# VestibularH2.net
KiCad netlist of a schematic drawn in EAGLE
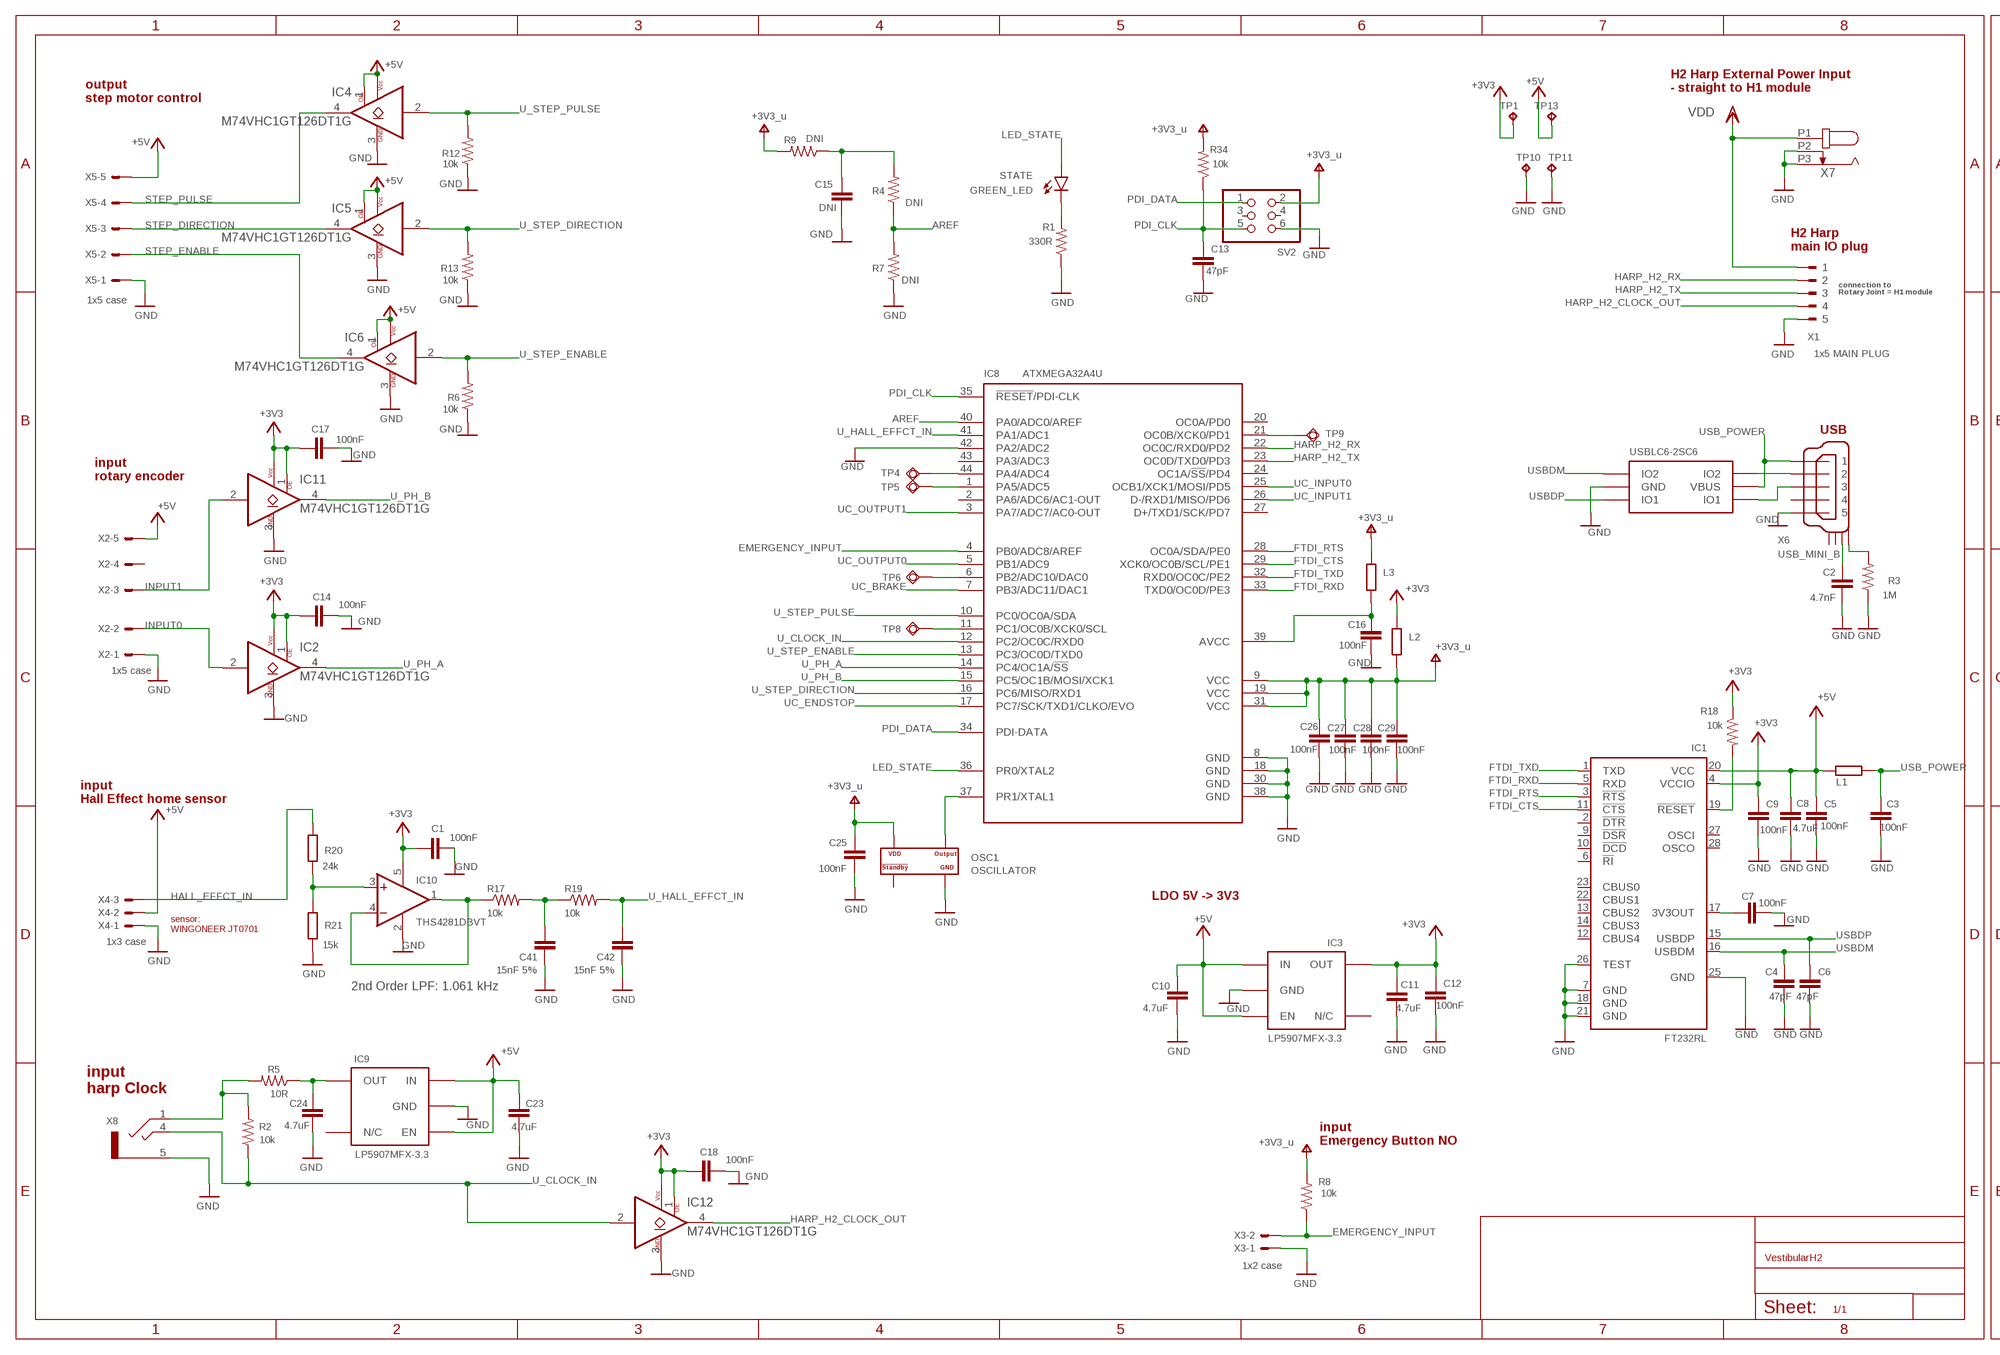
[diagram p0: schematic, sheet 1, part 1 of 2]
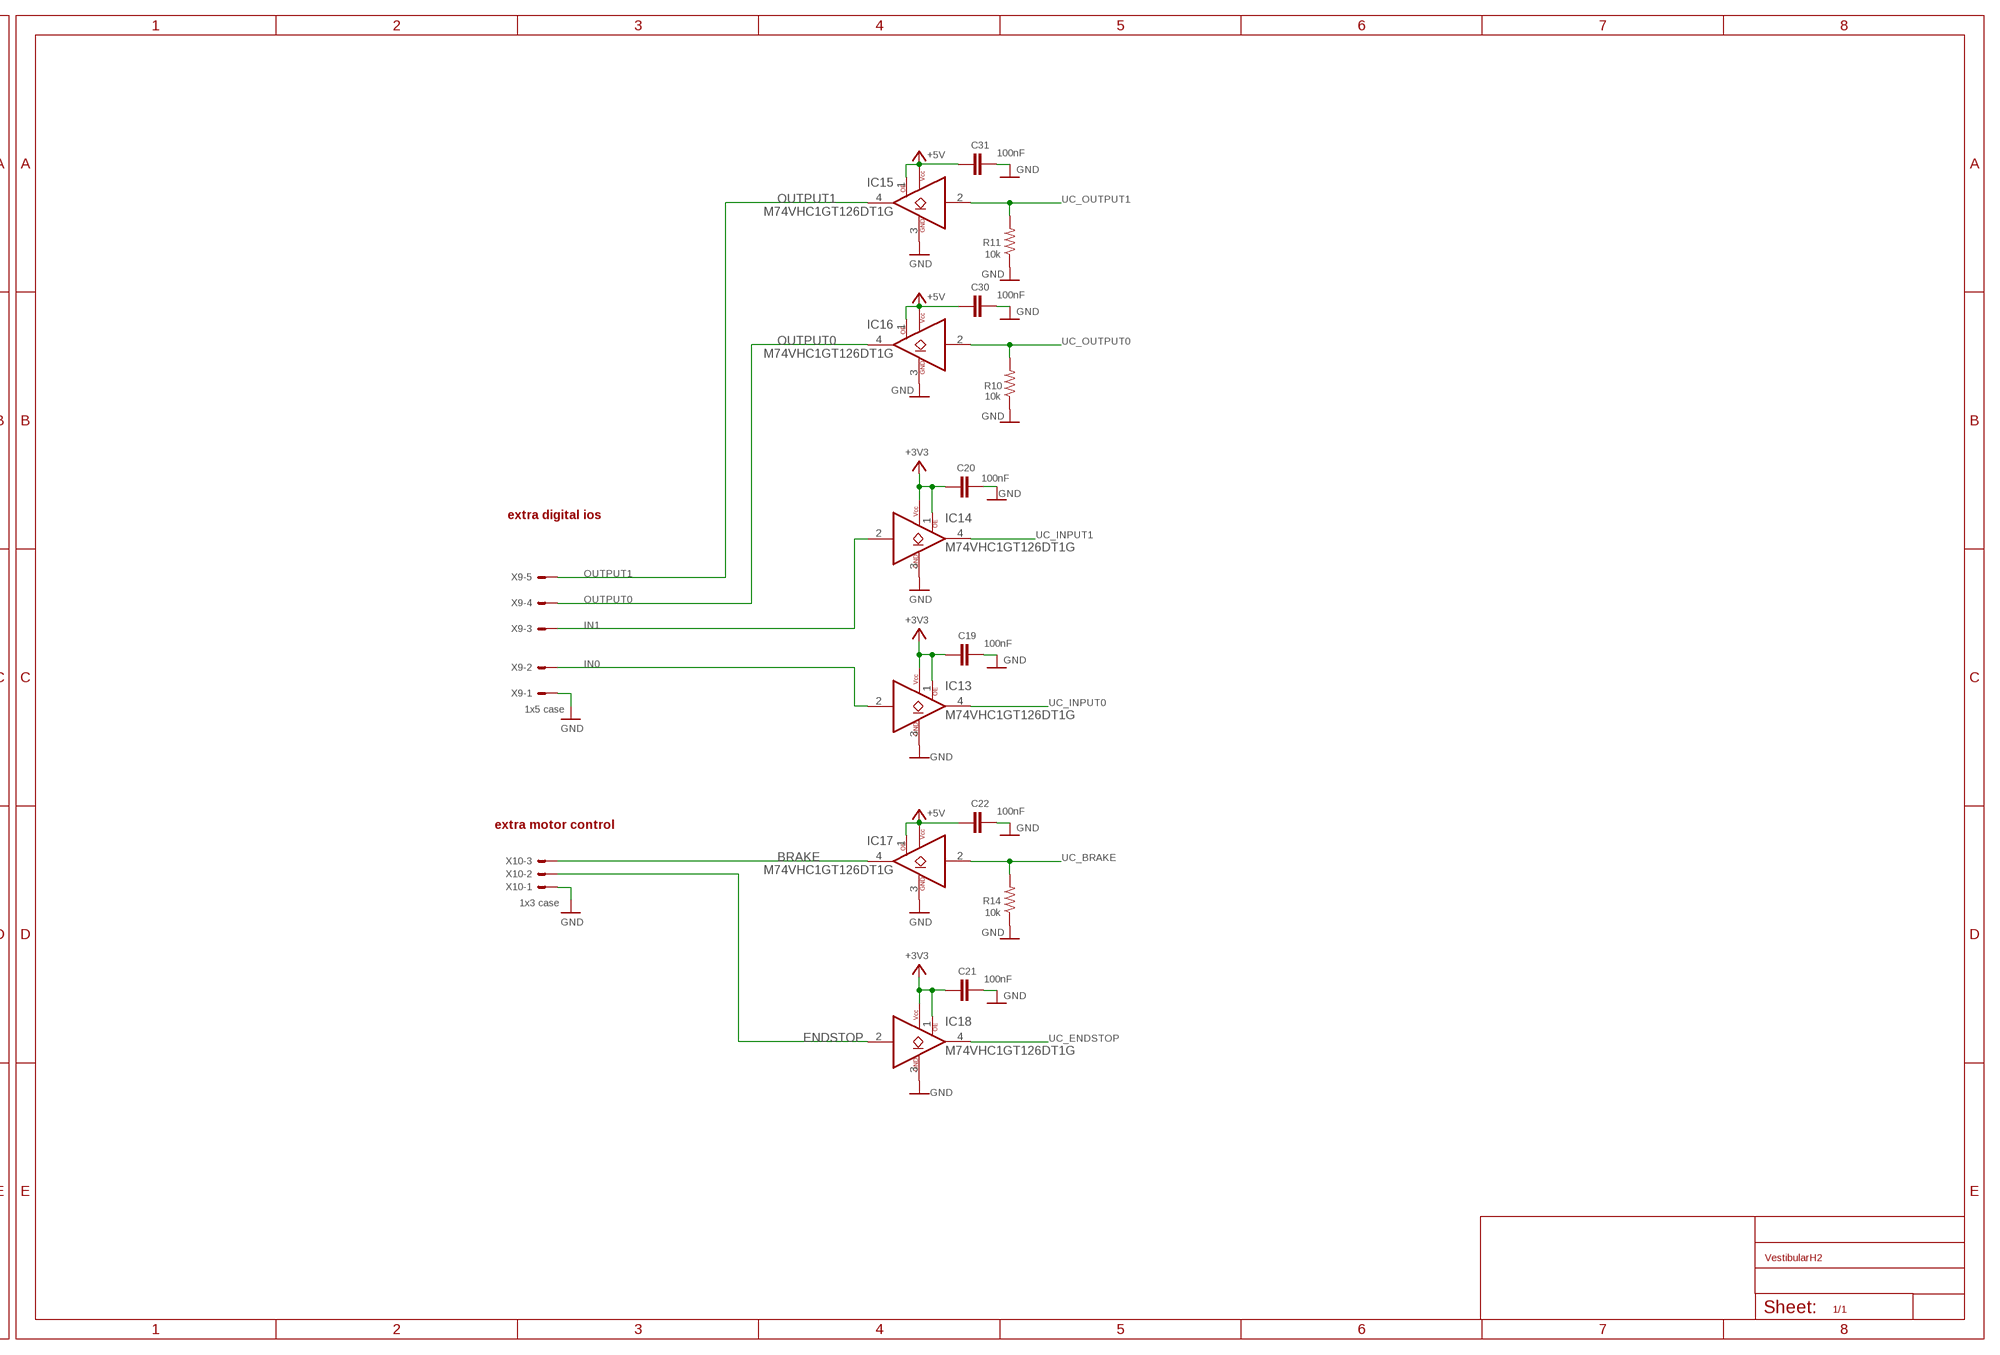
[diagram p1: schematic, sheet 1, part 2 of 2]

(export (version "E")
  (design (tool "Eeschema 10.0.6"))
  (components
    (comp (ref "C1")
      (value "100nF")
      (footprint "eagle-import:C0402K")
      (fields (field (name "MPN") "C1005X7R1H104K050BB"))
      (libsource (lib "eagle-import") (part "C-EUC0402K"))
    )
    (comp (ref "C2")
      (value "4.7nF")
      (footprint "eagle-import:C0402K")
      (fields (field (name "MPN") "CC0402KRX7R8BB472"))
      (libsource (lib "eagle-import") (part "C-EUC0402K"))
    )
    (comp (ref "C3")
      (value "100nF")
      (footprint "eagle-import:C0402K")
      (fields (field (name "MPN") "C1005X7R1H104K050BB"))
      (libsource (lib "eagle-import") (part "C-EUC0402K"))
    )
    (comp (ref "C4")
      (value "47pF")
      (footprint "eagle-import:C0402K")
      (fields (field (name "MPN") "04025A470JAT2A"))
      (libsource (lib "eagle-import") (part "C-EUC0402K"))
    )
    (comp (ref "C5")
      (value "100nF")
      (footprint "eagle-import:C0402K")
      (fields (field (name "MPN") "C1005X7R1H104K050BB"))
      (libsource (lib "eagle-import") (part "C-EUC0402K"))
    )
    (comp (ref "C6")
      (value "47pF")
      (footprint "eagle-import:C0402K")
      (fields (field (name "MPN") "04025A470JAT2A"))
      (libsource (lib "eagle-import") (part "C-EUC0402K"))
    )
    (comp (ref "C7")
      (value "100nF")
      (footprint "eagle-import:C0402K")
      (fields (field (name "MPN") "C1005X7R1H104K050BB"))
      (libsource (lib "eagle-import") (part "C-EUC0402K"))
    )
    (comp (ref "C8")
      (value "4.7uF")
      (footprint "eagle-import:C0603K")
      (fields (field (name "MPN") "C1608X6S1C475K080AC"))
      (libsource (lib "eagle-import") (part "C-EUC0603K"))
    )
    (comp (ref "C9")
      (value "100nF")
      (footprint "eagle-import:C0402K")
      (fields (field (name "MPN") "C1005X7R1H104K050BB"))
      (libsource (lib "eagle-import") (part "C-EUC0402K"))
    )
    (comp (ref "C10")
      (value "4.7uF")
      (footprint "eagle-import:C0603K")
      (fields (field (name "MPN") "C1608X6S1C475K080AC"))
      (libsource (lib "eagle-import") (part "C-EUC0603K"))
    )
    (comp (ref "C11")
      (value "4.7uF")
      (footprint "eagle-import:C0603K")
      (fields (field (name "MPN") "C1608X6S1C475K080AC"))
      (libsource (lib "eagle-import") (part "C-EUC0603K"))
    )
    (comp (ref "C12")
      (value "100nF")
      (footprint "eagle-import:C0402K")
      (fields (field (name "MPN") "C1005X7R1H104K050BB"))
      (libsource (lib "eagle-import") (part "C-EUC0402K"))
    )
    (comp (ref "C13")
      (value "47pF")
      (footprint "eagle-import:C0402K")
      (fields (field (name "MPN") "04025A470JAT2A"))
      (libsource (lib "eagle-import") (part "C-EUC0402K"))
    )
    (comp (ref "C14")
      (value "100nF")
      (footprint "eagle-import:C0402K")
      (fields (field (name "MPN") "C1005X7R1H104K050BB"))
      (libsource (lib "eagle-import") (part "C-EUC0402K"))
    )
    (comp (ref "C15")
      (value "DNI")
      (footprint "eagle-import:C0603K")
      (libsource (lib "eagle-import") (part "C-EUC0603K"))
    )
    (comp (ref "C16")
      (value "100nF")
      (footprint "eagle-import:C0402K")
      (fields (field (name "MPN") "C1005X7R1H104K050BB"))
      (libsource (lib "eagle-import") (part "C-EUC0402K"))
    )
    (comp (ref "C17")
      (value "100nF")
      (footprint "eagle-import:C0402K")
      (fields (field (name "MPN") "C1005X7R1H104K050BB"))
      (libsource (lib "eagle-import") (part "C-EUC0402K"))
    )
    (comp (ref "C18")
      (value "100nF")
      (footprint "eagle-import:C0402K")
      (fields (field (name "MPN") "C1005X7R1H104K050BB"))
      (libsource (lib "eagle-import") (part "C-EUC0402K"))
    )
    (comp (ref "C19")
      (value "100nF")
      (footprint "eagle-import:C0402K")
      (fields (field (name "MPN") "C1005X7R1H104K050BB"))
      (libsource (lib "eagle-import") (part "C-EUC0402K"))
    )
    (comp (ref "C20")
      (value "100nF")
      (footprint "eagle-import:C0402K")
      (fields (field (name "MPN") "C1005X7R1H104K050BB"))
      (libsource (lib "eagle-import") (part "C-EUC0402K"))
    )
    (comp (ref "C21")
      (value "100nF")
      (footprint "eagle-import:C0402K")
      (fields (field (name "MPN") "C1005X7R1H104K050BB"))
      (libsource (lib "eagle-import") (part "C-EUC0402K"))
    )
    (comp (ref "C22")
      (value "100nF")
      (footprint "eagle-import:C0402K")
      (fields (field (name "MPN") "C1005X7R1H104K050BB"))
      (libsource (lib "eagle-import") (part "C-EUC0402K"))
    )
    (comp (ref "C23")
      (value "4.7uF")
      (footprint "eagle-import:C0603K")
      (fields (field (name "MPN") "C1608X6S1C475K080AC"))
      (libsource (lib "eagle-import") (part "C-EUC0603K"))
    )
    (comp (ref "C24")
      (value "4.7uF")
      (footprint "eagle-import:C0603K")
      (fields (field (name "MPN") "C1608X6S1C475K080AC"))
      (libsource (lib "eagle-import") (part "C-EUC0603K"))
    )
    (comp (ref "C25")
      (value "100nF")
      (footprint "eagle-import:C0402K")
      (fields (field (name "MPN") "C1005X7R1H104K050BB"))
      (libsource (lib "eagle-import") (part "C-EUC0402K"))
    )
    (comp (ref "C26")
      (value "100nF")
      (footprint "eagle-import:C0402K")
      (fields (field (name "MPN") "C1005X7R1H104K050BB"))
      (libsource (lib "eagle-import") (part "C-EUC0402K"))
    )
    (comp (ref "C27")
      (value "100nF")
      (footprint "eagle-import:C0402K")
      (fields (field (name "MPN") "C1005X7R1H104K050BB"))
      (libsource (lib "eagle-import") (part "C-EUC0402K"))
    )
    (comp (ref "C28")
      (value "100nF")
      (footprint "eagle-import:C0402K")
      (fields (field (name "MPN") "C1005X7R1H104K050BB"))
      (libsource (lib "eagle-import") (part "C-EUC0402K"))
    )
    (comp (ref "C29")
      (value "100nF")
      (footprint "eagle-import:C0402K")
      (fields (field (name "MPN") "C1005X7R1H104K050BB"))
      (libsource (lib "eagle-import") (part "C-EUC0402K"))
    )
    (comp (ref "C30")
      (value "100nF")
      (footprint "eagle-import:C0402K")
      (fields (field (name "MPN") "C1005X7R1H104K050BB"))
      (libsource (lib "eagle-import") (part "C-EUC0402K"))
    )
    (comp (ref "C31")
      (value "100nF")
      (footprint "eagle-import:C0402K")
      (fields (field (name "MPN") "C1005X7R1H104K050BB"))
      (libsource (lib "eagle-import") (part "C-EUC0402K"))
    )
    (comp (ref "C41")
      (value "15nF 5%")
      (footprint "eagle-import:C0402K")
      (fields (field (name "MPN") "CGA2B3X7R1V153K050BB"))
      (libsource (lib "eagle-import") (part "C-EUC0402K"))
    )
    (comp (ref "C42")
      (value "15nF 5%")
      (footprint "eagle-import:C0402K")
      (fields (field (name "MPN") "CGA2B3X7R1V153K050BB"))
      (libsource (lib "eagle-import") (part "C-EUC0402K"))
    )
    (comp (ref "IC1")
      (value "FT232RL")
      (footprint "eagle-import:SSOP28")
      (libsource (lib "eagle-import") (part "FT232RL"))
    )
    (comp (ref "IC2")
      (value "M74VHC1GT126DT1G")
      (footprint "eagle-import:TSOP-5")
      (libsource (lib "eagle-import") (part "M74VHC1GT126DT1G"))
    )
    (comp (ref "IC3")
      (value "LP5907MFX-3.3")
      (footprint "eagle-import:TSOT23-5")
      (fields (field (name "MPN") "LP5907MFX-3.3/NOPB"))
      (libsource (lib "eagle-import") (part "TLV700XX"))
    )
    (comp (ref "IC4")
      (value "M74VHC1GT126DT1G")
      (footprint "eagle-import:TSOP-5")
      (libsource (lib "eagle-import") (part "M74VHC1GT126DT1G"))
    )
    (comp (ref "IC5")
      (value "M74VHC1GT126DT1G")
      (footprint "eagle-import:TSOP-5")
      (libsource (lib "eagle-import") (part "M74VHC1GT126DT1G"))
    )
    (comp (ref "IC6")
      (value "M74VHC1GT126DT1G")
      (footprint "eagle-import:TSOP-5")
      (libsource (lib "eagle-import") (part "M74VHC1GT126DT1G"))
    )
    (comp (ref "IC7")
      (value "USBLC6-2SC6")
      (footprint "eagle-import:SOT23-6L")
      (libsource (lib "eagle-import") (part "USBLC6-2SC6"))
    )
    (comp (ref "IC8")
      (value "ATXMEGA32A4U")
      (footprint "eagle-import:TQFP44")
      (fields (field (name "MPN") "ATXMEGA32A4U-AUR"))
      (libsource (lib "eagle-import") (part "XMEGA-A4_AT-XMEGA-XXA4-AUTQFP44"))
    )
    (comp (ref "IC9")
      (value "LP5907MFX-3.3")
      (footprint "eagle-import:TSOT23-5")
      (fields (field (name "MPN") "LP5907MFX-3.3/NOPB"))
      (libsource (lib "eagle-import") (part "TLV700XX"))
    )
    (comp (ref "IC10")
      (value "THS4281DBVT")
      (footprint "eagle-import:SOT23-5")
      (libsource (lib "eagle-import") (part "OPA365"))
    )
    (comp (ref "IC11")
      (value "M74VHC1GT126DT1G")
      (footprint "eagle-import:TSOP-5")
      (libsource (lib "eagle-import") (part "M74VHC1GT126DT1G"))
    )
    (comp (ref "IC12")
      (value "M74VHC1GT126DT1G")
      (footprint "eagle-import:TSOP-5")
      (libsource (lib "eagle-import") (part "M74VHC1GT126DT1G"))
    )
    (comp (ref "IC13")
      (value "M74VHC1GT126DT1G")
      (footprint "eagle-import:TSOP-5")
      (libsource (lib "eagle-import") (part "M74VHC1GT126DT1G"))
    )
    (comp (ref "IC14")
      (value "M74VHC1GT126DT1G")
      (footprint "eagle-import:TSOP-5")
      (libsource (lib "eagle-import") (part "M74VHC1GT126DT1G"))
    )
    (comp (ref "IC15")
      (value "M74VHC1GT126DT1G")
      (footprint "eagle-import:TSOP-5")
      (libsource (lib "eagle-import") (part "M74VHC1GT126DT1G"))
    )
    (comp (ref "IC16")
      (value "M74VHC1GT126DT1G")
      (footprint "eagle-import:TSOP-5")
      (libsource (lib "eagle-import") (part "M74VHC1GT126DT1G"))
    )
    (comp (ref "IC17")
      (value "M74VHC1GT126DT1G")
      (footprint "eagle-import:TSOP-5")
      (libsource (lib "eagle-import") (part "M74VHC1GT126DT1G"))
    )
    (comp (ref "IC18")
      (value "M74VHC1GT126DT1G")
      (footprint "eagle-import:TSOP-5")
      (libsource (lib "eagle-import") (part "M74VHC1GT126DT1G"))
    )
    (comp (ref "L1")
      (value "40R@100MHz")
      (footprint "eagle-import:R0805")
      (fields (field (name "MPN") "MI0805K400R-10"))
      (libsource (lib "eagle-import") (part "R-EU_R0805"))
    )
    (comp (ref "L2")
      (value "40R@100MHz")
      (footprint "eagle-import:R0805")
      (fields (field (name "MPN") "MI0805K400R-10"))
      (libsource (lib "eagle-import") (part "R-EU_R0805"))
    )
    (comp (ref "L3")
      (value "40R@100MHz")
      (footprint "eagle-import:R0805")
      (fields (field (name "MPN") "MI0805K400R-10"))
      (libsource (lib "eagle-import") (part "R-EU_R0805"))
    )
    (comp (ref "OSC1")
      (value "OSCILLATOR")
      (footprint "eagle-import:OSCILLATOR_3.2X2.5")
      (fields (field (name "MPN") "DSC1001CI5-032.0000"))
      (libsource (lib "eagle-import") (part "OSCILLATOR"))
    )
    (comp (ref "R1")
      (value "330R")
      (footprint "eagle-import:R0402")
      (fields (field (name "MPN") "RC0402FR-07330RL"))
      (libsource (lib "eagle-import") (part "R-US_R0402"))
    )
    (comp (ref "R2")
      (value "10k")
      (footprint "eagle-import:R0402")
      (fields (field (name "MPN") "CRCW040210K0FKED"))
      (libsource (lib "eagle-import") (part "R-US_R0402"))
    )
    (comp (ref "R3")
      (value "1M")
      (footprint "eagle-import:R0402")
      (fields (field (name "MPN") "CRCW04021M00FKED"))
      (libsource (lib "eagle-import") (part "R-US_R0402"))
    )
    (comp (ref "R4")
      (value "DNI")
      (footprint "eagle-import:R0402")
      (libsource (lib "eagle-import") (part "R-US_R0402"))
    )
    (comp (ref "R5")
      (value "10R")
      (footprint "eagle-import:R0402")
      (fields (field (name "MPN") "ERJ-PA2J100X "))
      (libsource (lib "eagle-import") (part "R-US_R0402"))
    )
    (comp (ref "R6")
      (value "10k")
      (footprint "eagle-import:R0402")
      (fields (field (name "MPN") "CRCW040210K0FKED"))
      (libsource (lib "eagle-import") (part "R-US_R0402"))
    )
    (comp (ref "R7")
      (value "DNI")
      (footprint "eagle-import:R0402")
      (libsource (lib "eagle-import") (part "R-US_R0402"))
    )
    (comp (ref "R8")
      (value "10k")
      (footprint "eagle-import:R0402")
      (fields (field (name "MPN") "CRCW040210K0FKED"))
      (libsource (lib "eagle-import") (part "R-US_R0402"))
    )
    (comp (ref "R9")
      (value "DNI")
      (footprint "eagle-import:R0402")
      (libsource (lib "eagle-import") (part "R-US_R0402"))
    )
    (comp (ref "R10")
      (value "10k")
      (footprint "eagle-import:R0402")
      (fields (field (name "MPN") "CRCW040210K0FKED"))
      (libsource (lib "eagle-import") (part "R-US_R0402"))
    )
    (comp (ref "R11")
      (value "10k")
      (footprint "eagle-import:R0402")
      (fields (field (name "MPN") "CRCW040210K0FKED"))
      (libsource (lib "eagle-import") (part "R-US_R0402"))
    )
    (comp (ref "R12")
      (value "10k")
      (footprint "eagle-import:R0402")
      (fields (field (name "MPN") "CRCW040210K0FKED"))
      (libsource (lib "eagle-import") (part "R-US_R0402"))
    )
    (comp (ref "R13")
      (value "10k")
      (footprint "eagle-import:R0402")
      (fields (field (name "MPN") "CRCW040210K0FKED"))
      (libsource (lib "eagle-import") (part "R-US_R0402"))
    )
    (comp (ref "R14")
      (value "10k")
      (footprint "eagle-import:R0402")
      (fields (field (name "MPN") "CRCW040210K0FKED"))
      (libsource (lib "eagle-import") (part "R-US_R0402"))
    )
    (comp (ref "R17")
      (value "10k")
      (footprint "eagle-import:R0402")
      (fields (field (name "MPN") "CRCW040210K0FKED"))
      (libsource (lib "eagle-import") (part "R-US_R0402"))
    )
    (comp (ref "R18")
      (value "10k")
      (footprint "eagle-import:R0402")
      (fields (field (name "MPN") "CRCW040210K0FKED"))
      (libsource (lib "eagle-import") (part "R-US_R0402"))
    )
    (comp (ref "R19")
      (value "10k")
      (footprint "eagle-import:R0402")
      (fields (field (name "MPN") "CRCW040210K0FKED"))
      (libsource (lib "eagle-import") (part "R-US_R0402"))
    )
    (comp (ref "R20")
      (value "24k")
      (footprint "eagle-import:R0402")
      (fields (field (name "MPN") "ERJ-2RKF2402X"))
      (libsource (lib "eagle-import") (part "R-EU_R0402"))
    )
    (comp (ref "R21")
      (value "15k")
      (footprint "eagle-import:R0402")
      (fields (field (name "MPN") "ERJ-2RKF1502X"))
      (libsource (lib "eagle-import") (part "R-EU_R0402"))
    )
    (comp (ref "R34")
      (value "10k")
      (footprint "eagle-import:R0402")
      (fields (field (name "MPN") "CRCW040210K0FKED"))
      (libsource (lib "eagle-import") (part "R-US_R0402"))
    )
    (comp (ref "STATE")
      (value "GREEN_LED")
      (footprint "eagle-import:CHIP-LED0603")
      (fields (field (name "MPN") "LTST-C191KGKT"))
      (libsource (lib "eagle-import") (part "LEDCHIP-LED0603"))
    )
    (comp (ref "SV2")
      (value "PINHD-2X3")
      (footprint "eagle-import:2X03")
      (fields (field (name "MPN") "609-3210-ND"))
      (libsource (lib "eagle-import") (part "PINHD-2X3"))
    )
    (comp (ref "TP1")
      (value "NO_COMPONENT")
      (footprint "eagle-import:B1,27")
      (libsource (lib "eagle-import") (part "TPB1,27"))
    )
    (comp (ref "TP4")
      (value "NO_COMPONENT")
      (footprint "eagle-import:TP11R")
      (libsource (lib "eagle-import") (part "TPSQTP11R"))
    )
    (comp (ref "TP5")
      (value "NO_COMPONENT")
      (footprint "eagle-import:TP11R")
      (libsource (lib "eagle-import") (part "TPSQTP11R"))
    )
    (comp (ref "TP6")
      (value "NO_COMPONENT")
      (footprint "eagle-import:TP11R")
      (libsource (lib "eagle-import") (part "TPSQTP11R"))
    )
    (comp (ref "TP8")
      (value "NO_COMPONENT")
      (footprint "eagle-import:TP11R")
      (libsource (lib "eagle-import") (part "TPSQTP11R"))
    )
    (comp (ref "TP9")
      (value "NO_COMPONENT")
      (footprint "eagle-import:TP11R")
      (libsource (lib "eagle-import") (part "TPSQTP11R"))
    )
    (comp (ref "TP10")
      (value "NO_COMPONENT")
      (footprint "eagle-import:B1,27")
      (libsource (lib "eagle-import") (part "TPB1,27"))
    )
    (comp (ref "TP11")
      (value "NO_COMPONENT")
      (footprint "eagle-import:B1,27")
      (libsource (lib "eagle-import") (part "TPB1,27"))
    )
    (comp (ref "TP13")
      (value "NO_COMPONENT")
      (footprint "eagle-import:B1,27")
      (libsource (lib "eagle-import") (part "TPB1,27"))
    )
    (comp (ref "X1")
      (value "1x5 MAIN PLUG")
      (footprint "eagle-import:90G-5")
      (fields (field (name "MPN") "20.155MH/5-E"))
      (libsource (lib "eagle-import") (part "90G-5"))
    )
    (comp (ref "X2")
      (value "1x5 case")
      (footprint "eagle-import:22-23-2051")
      (fields (field (name "MPN") "282834-5") (field (name "OEPS") "OEPS070041"))
      (libsource (lib "eagle-import") (part "22-23-2051"))
    )
    (comp (ref "X3")
      (value "1x2 case")
      (footprint "eagle-import:22-23-2021")
      (fields (field (name "MPN") "282834-2"))
      (libsource (lib "eagle-import") (part "22-23-2021"))
    )
    (comp (ref "X4")
      (value "1x3 case")
      (footprint "eagle-import:22-23-2031")
      (fields (field (name "MPN") "282834-3") (field (name "OEPS") "OEPS070035"))
      (libsource (lib "eagle-import") (part "22-23-2031"))
    )
    (comp (ref "X5")
      (value "1x5 case")
      (footprint "eagle-import:22-23-2051")
      (fields (field (name "MPN") "282834-5") (field (name "OEPS") "OEPS070041"))
      (libsource (lib "eagle-import") (part "22-23-2051"))
    )
    (comp (ref "X6")
      (value "USB_MINI_B")
      (footprint "eagle-import:240-0002-1")
      (fields (field (name "MPN") "UX60-MB-5S8"))
      (libsource (lib "eagle-import") (part "USB_MINI_B"))
    )
    (comp (ref "X7")
      (value "DC_JACK2.1MM")
      (footprint "eagle-import:DC_POWER_INPUT_2.1MM")
      (fields (field (name "MPN") "163-179PH-EX"))
      (libsource (lib "eagle-import") (part "DC_JACK2.1MM"))
    )
    (comp (ref "X8")
      (value "CLCK_JACK")
      (footprint "eagle-import:35RASMT2BHNTRX")
      (fields (field (name "MPN") "35RASMT2BHNTRX"))
      (libsource (lib "eagle-import") (part "STEREO_JACK"))
    )
    (comp (ref "X9")
      (value "1x5 case")
      (footprint "eagle-import:22-23-2051")
      (fields (field (name "MPN") "282834-5") (field (name "OEPS") "OEPS070041"))
      (libsource (lib "eagle-import") (part "22-23-2051"))
    )
    (comp (ref "X10")
      (value "1x3 case")
      (footprint "eagle-import:22-23-2031")
      (fields (field (name "MPN") "282834-3") (field (name "OEPS") "OEPS070035"))
      (libsource (lib "eagle-import") (part "22-23-2031"))
    )
  )
  (nets
    (net (code "1") (name "+3V3") (class "Default")
      (node (ref "C1") (pin "1") (pinfunction "1_1") (pintype "passive"))
      (node (ref "C11") (pin "1") (pinfunction "1_1") (pintype "passive"))
      (node (ref "C12") (pin "1") (pinfunction "1_1") (pintype "passive"))
      (node (ref "C14") (pin "1") (pinfunction "1_1") (pintype "passive"))
      (node (ref "C17") (pin "1") (pinfunction "1_1") (pintype "passive"))
      (node (ref "C18") (pin "1") (pinfunction "1_1") (pintype "passive"))
      (node (ref "C19") (pin "1") (pinfunction "1_1") (pintype "passive"))
      (node (ref "C20") (pin "1") (pinfunction "1_1") (pintype "passive"))
      (node (ref "C21") (pin "1") (pinfunction "1_1") (pintype "passive"))
      (node (ref "C9") (pin "1") (pinfunction "1_1") (pintype "passive"))
      (node (ref "IC1") (pin "4") (pinfunction "VCCIO_4") (pintype "power_in"))
      (node (ref "IC10") (pin "5") (pinfunction "V+_5") (pintype "power_in"))
      (node (ref "IC11") (pin "1") (pinfunction "OE_1") (pintype "bidirectional"))
      (node (ref "IC11") (pin "5") (pinfunction "VCC_5") (pintype "bidirectional"))
      (node (ref "IC12") (pin "1") (pinfunction "OE_1") (pintype "bidirectional"))
      (node (ref "IC12") (pin "5") (pinfunction "VCC_5") (pintype "bidirectional"))
      (node (ref "IC13") (pin "1") (pinfunction "OE_1") (pintype "bidirectional"))
      (node (ref "IC13") (pin "5") (pinfunction "VCC_5") (pintype "bidirectional"))
      (node (ref "IC14") (pin "1") (pinfunction "OE_1") (pintype "bidirectional"))
      (node (ref "IC14") (pin "5") (pinfunction "VCC_5") (pintype "bidirectional"))
      (node (ref "IC18") (pin "1") (pinfunction "OE_1") (pintype "bidirectional"))
      (node (ref "IC18") (pin "5") (pinfunction "VCC_5") (pintype "bidirectional"))
      (node (ref "IC2") (pin "1") (pinfunction "OE_1") (pintype "bidirectional"))
      (node (ref "IC2") (pin "5") (pinfunction "VCC_5") (pintype "bidirectional"))
      (node (ref "IC3") (pin "5") (pinfunction "OUT_5") (pintype "bidirectional"))
      (node (ref "L2") (pin "2") (pinfunction "2_2") (pintype "passive"))
      (node (ref "R18") (pin "1") (pinfunction "1_1") (pintype "passive"))
      (node (ref "TP1") (pin "TP") (pinfunction "TP_TP") (pintype "input"))
    )
    (net (code "2") (name "+3V3_u") (class "Default")
      (node (ref "C25") (pin "1") (pinfunction "1_1") (pintype "passive"))
      (node (ref "C26") (pin "1") (pinfunction "1_1") (pintype "passive"))
      (node (ref "C27") (pin "1") (pinfunction "1_1") (pintype "passive"))
      (node (ref "C28") (pin "1") (pinfunction "1_1") (pintype "passive"))
      (node (ref "C29") (pin "1") (pinfunction "1_1") (pintype "passive"))
      (node (ref "IC8") (pin "19") (pinfunction "VCC_19") (pintype "power_in"))
      (node (ref "IC8") (pin "31") (pinfunction "VCC_31") (pintype "power_in"))
      (node (ref "IC8") (pin "9") (pinfunction "VCC_9") (pintype "power_in"))
      (node (ref "L2") (pin "1") (pinfunction "1_1") (pintype "passive"))
      (node (ref "L3") (pin "2") (pinfunction "2_2") (pintype "passive"))
      (node (ref "OSC1") (pin "P$4") (pinfunction "VDD_P$4") (pintype "passive"))
      (node (ref "R34") (pin "2") (pinfunction "2_2") (pintype "passive"))
      (node (ref "R8") (pin "2") (pinfunction "2_2") (pintype "passive"))
      (node (ref "R9") (pin "2") (pinfunction "2_2") (pintype "passive"))
      (node (ref "SV2") (pin "2") (pinfunction "2_2") (pintype "passive"))
    )
    (net (code "3") (name "+5V") (class "Default")
      (node (ref "C10") (pin "1") (pinfunction "1_1") (pintype "passive"))
      (node (ref "C22") (pin "1") (pinfunction "1_1") (pintype "passive"))
      (node (ref "C23") (pin "1") (pinfunction "1_1") (pintype "passive"))
      (node (ref "C30") (pin "1") (pinfunction "1_1") (pintype "passive"))
      (node (ref "C31") (pin "1") (pinfunction "1_1") (pintype "passive"))
      (node (ref "C5") (pin "1") (pinfunction "1_1") (pintype "passive"))
      (node (ref "C8") (pin "1") (pinfunction "1_1") (pintype "passive"))
      (node (ref "IC1") (pin "20") (pinfunction "VCC_20") (pintype "power_in"))
      (node (ref "IC15") (pin "1") (pinfunction "OE_1") (pintype "bidirectional"))
      (node (ref "IC15") (pin "5") (pinfunction "VCC_5") (pintype "bidirectional"))
      (node (ref "IC16") (pin "1") (pinfunction "OE_1") (pintype "bidirectional"))
      (node (ref "IC16") (pin "5") (pinfunction "VCC_5") (pintype "bidirectional"))
      (node (ref "IC17") (pin "1") (pinfunction "OE_1") (pintype "bidirectional"))
      (node (ref "IC17") (pin "5") (pinfunction "VCC_5") (pintype "bidirectional"))
      (node (ref "IC3") (pin "1") (pinfunction "IN_1") (pintype "bidirectional"))
      (node (ref "IC3") (pin "3") (pinfunction "EN_3") (pintype "bidirectional"))
      (node (ref "IC4") (pin "1") (pinfunction "OE_1") (pintype "bidirectional"))
      (node (ref "IC4") (pin "5") (pinfunction "VCC_5") (pintype "bidirectional"))
      (node (ref "IC5") (pin "1") (pinfunction "OE_1") (pintype "bidirectional"))
      (node (ref "IC5") (pin "5") (pinfunction "VCC_5") (pintype "bidirectional"))
      (node (ref "IC6") (pin "1") (pinfunction "OE_1") (pintype "bidirectional"))
      (node (ref "IC6") (pin "5") (pinfunction "VCC_5") (pintype "bidirectional"))
      (node (ref "IC9") (pin "1") (pinfunction "IN_1") (pintype "bidirectional"))
      (node (ref "IC9") (pin "3") (pinfunction "EN_3") (pintype "bidirectional"))
      (node (ref "L1") (pin "1") (pinfunction "1_1") (pintype "passive"))
      (node (ref "TP13") (pin "TP") (pinfunction "TP_TP") (pintype "input"))
      (node (ref "X2") (pin "5") (pinfunction "S_5") (pintype "passive"))
      (node (ref "X4") (pin "2") (pinfunction "S_2") (pintype "passive"))
      (node (ref "X5") (pin "5") (pinfunction "S_5") (pintype "passive"))
    )
    (net (code "4") (name "/AREF") (class "Default")
      (node (ref "IC8") (pin "40") (pinfunction "PA0/ADC0/AREF_40") (pintype "bidirectional"))
      (node (ref "R4") (pin "1") (pinfunction "1_1") (pintype "passive"))
      (node (ref "R7") (pin "2") (pinfunction "2_2") (pintype "passive"))
    )
    (net (code "5") (name "/BRAKE") (class "Default")
      (node (ref "IC17") (pin "4") (pinfunction "Y_4") (pintype "bidirectional"))
      (node (ref "X10") (pin "3") (pinfunction "S_3") (pintype "passive"))
    )
    (net (code "6") (name "/EMERGENCY_INPUT") (class "Default")
      (node (ref "IC8") (pin "4") (pinfunction "PB0/ADC8/AREF_4") (pintype "bidirectional"))
      (node (ref "R8") (pin "1") (pinfunction "1_1") (pintype "passive"))
      (node (ref "X3") (pin "2") (pinfunction "S_2") (pintype "passive"))
    )
    (net (code "7") (name "/ENDSTOP") (class "Default")
      (node (ref "IC18") (pin "2") (pinfunction "A_2") (pintype "bidirectional"))
      (node (ref "X10") (pin "2") (pinfunction "S_2") (pintype "passive"))
    )
    (net (code "8") (name "/FTDI_CTS") (class "Default")
      (node (ref "IC1") (pin "11") (pinfunction "~{CTS}_11") (pintype "input"))
      (node (ref "IC8") (pin "29") (pinfunction "XCK0/OC0B/SCL/PE1_29") (pintype "bidirectional"))
    )
    (net (code "9") (name "/FTDI_RTS") (class "Default")
      (node (ref "IC1") (pin "3") (pinfunction "~{RTS}_3") (pintype "output"))
      (node (ref "IC8") (pin "28") (pinfunction "OC0A/SDA/PE0_28") (pintype "bidirectional"))
    )
    (net (code "10") (name "/FTDI_RXD") (class "Default")
      (node (ref "IC1") (pin "5") (pinfunction "RXD_5") (pintype "input"))
      (node (ref "IC8") (pin "33") (pinfunction "TXD0/OC0D/PE3_33") (pintype "bidirectional"))
    )
    (net (code "11") (name "/FTDI_TXD") (class "Default")
      (node (ref "IC1") (pin "1") (pinfunction "TXD_1") (pintype "output"))
      (node (ref "IC8") (pin "32") (pinfunction "RXD0/OC0C/PE2_32") (pintype "bidirectional"))
    )
    (net (code "12") (name "/HALL_EFFCT_IN") (class "Default")
      (node (ref "R20") (pin "2") (pinfunction "2_2") (pintype "passive"))
      (node (ref "X4") (pin "3") (pinfunction "S_3") (pintype "passive"))
    )
    (net (code "13") (name "/HARP_H2_CLOCK_OUT") (class "Default")
      (node (ref "IC12") (pin "4") (pinfunction "Y_4") (pintype "bidirectional"))
      (node (ref "X1") (pin "4") (pinfunction "4_4") (pintype "passive"))
    )
    (net (code "14") (name "/HARP_H2_RX") (class "Default")
      (node (ref "IC8") (pin "22") (pinfunction "OC0C/RXD0/PD2_22") (pintype "bidirectional"))
      (node (ref "X1") (pin "2") (pinfunction "2_2") (pintype "passive"))
    )
    (net (code "15") (name "/HARP_H2_TX") (class "Default")
      (node (ref "IC8") (pin "23") (pinfunction "OC0D/TXD0/PD3_23") (pintype "bidirectional"))
      (node (ref "X1") (pin "3") (pinfunction "3_3") (pintype "passive"))
    )
    (net (code "16") (name "/IN0") (class "Default")
      (node (ref "IC13") (pin "2") (pinfunction "A_2") (pintype "bidirectional"))
      (node (ref "X9") (pin "2") (pinfunction "S_2") (pintype "passive"))
    )
    (net (code "17") (name "/IN1") (class "Default")
      (node (ref "IC14") (pin "2") (pinfunction "A_2") (pintype "bidirectional"))
      (node (ref "X9") (pin "3") (pinfunction "S_3") (pintype "passive"))
    )
    (net (code "18") (name "/INPUT0") (class "Default")
      (node (ref "IC2") (pin "2") (pinfunction "A_2") (pintype "bidirectional"))
      (node (ref "X2") (pin "2") (pinfunction "S_2") (pintype "passive"))
    )
    (net (code "19") (name "/INPUT1") (class "Default")
      (node (ref "IC11") (pin "2") (pinfunction "A_2") (pintype "bidirectional"))
      (node (ref "X2") (pin "3") (pinfunction "S_3") (pintype "passive"))
    )
    (net (code "20") (name "/LED_STATE") (class "Default")
      (node (ref "IC8") (pin "36") (pinfunction "PR0/XTAL2_36") (pintype "bidirectional"))
      (node (ref "STATE") (pin "A") (pinfunction "A_A") (pintype "passive"))
    )
    (net (code "21") (name "/OUTPUT0") (class "Default")
      (node (ref "IC16") (pin "4") (pinfunction "Y_4") (pintype "bidirectional"))
      (node (ref "X9") (pin "4") (pinfunction "S_4") (pintype "passive"))
    )
    (net (code "22") (name "/OUTPUT1") (class "Default")
      (node (ref "IC15") (pin "4") (pinfunction "Y_4") (pintype "bidirectional"))
      (node (ref "X9") (pin "5") (pinfunction "S_5") (pintype "passive"))
    )
    (net (code "23") (name "/PDI_CLK") (class "Default")
      (node (ref "C13") (pin "1") (pinfunction "1_1") (pintype "passive"))
      (node (ref "IC8") (pin "35") (pinfunction "~{RESET}/PDI-CLK_35") (pintype "input"))
      (node (ref "R34") (pin "1") (pinfunction "1_1") (pintype "passive"))
      (node (ref "SV2") (pin "5") (pinfunction "5_5") (pintype "passive"))
    )
    (net (code "24") (name "/PDI_DATA") (class "Default")
      (node (ref "IC8") (pin "34") (pinfunction "PDI-DATA_34") (pintype "bidirectional"))
      (node (ref "SV2") (pin "1") (pinfunction "1_1") (pintype "passive"))
    )
    (net (code "25") (name "/STEP_DIRECTION") (class "Default")
      (node (ref "IC5") (pin "4") (pinfunction "Y_4") (pintype "bidirectional"))
      (node (ref "X5") (pin "3") (pinfunction "S_3") (pintype "passive"))
    )
    (net (code "26") (name "/STEP_ENABLE") (class "Default")
      (node (ref "IC6") (pin "4") (pinfunction "Y_4") (pintype "bidirectional"))
      (node (ref "X5") (pin "2") (pinfunction "S_2") (pintype "passive"))
    )
    (net (code "27") (name "/STEP_PULSE") (class "Default")
      (node (ref "IC4") (pin "4") (pinfunction "Y_4") (pintype "bidirectional"))
      (node (ref "X5") (pin "4") (pinfunction "S_4") (pintype "passive"))
    )
    (net (code "28") (name "/UC_BRAKE") (class "Default")
      (node (ref "IC17") (pin "2") (pinfunction "A_2") (pintype "bidirectional"))
      (node (ref "IC8") (pin "7") (pinfunction "PB3/ADC11/DAC1_7") (pintype "bidirectional"))
      (node (ref "R14") (pin "2") (pinfunction "2_2") (pintype "passive"))
    )
    (net (code "29") (name "/UC_ENDSTOP") (class "Default")
      (node (ref "IC18") (pin "4") (pinfunction "Y_4") (pintype "bidirectional"))
      (node (ref "IC8") (pin "17") (pinfunction "PC7/SCK/TXD1/CLKO/EVO_17") (pintype "bidirectional"))
    )
    (net (code "30") (name "/UC_INPUT0") (class "Default")
      (node (ref "IC13") (pin "4") (pinfunction "Y_4") (pintype "bidirectional"))
      (node (ref "IC8") (pin "25") (pinfunction "OCB1/XCK1/MOSI/PD5_25") (pintype "bidirectional"))
    )
    (net (code "31") (name "/UC_INPUT1") (class "Default")
      (node (ref "IC14") (pin "4") (pinfunction "Y_4") (pintype "bidirectional"))
      (node (ref "IC8") (pin "26") (pinfunction "D-/RXD1/MISO/PD6_26") (pintype "bidirectional"))
    )
    (net (code "32") (name "/UC_OUTPUT0") (class "Default")
      (node (ref "IC16") (pin "2") (pinfunction "A_2") (pintype "bidirectional"))
      (node (ref "IC8") (pin "5") (pinfunction "PB1/ADC9_5") (pintype "bidirectional"))
      (node (ref "R10") (pin "2") (pinfunction "2_2") (pintype "passive"))
    )
    (net (code "33") (name "/UC_OUTPUT1") (class "Default")
      (node (ref "IC15") (pin "2") (pinfunction "A_2") (pintype "bidirectional"))
      (node (ref "IC8") (pin "3") (pinfunction "PA7/ADC7/AC0-OUT_3") (pintype "bidirectional"))
      (node (ref "R11") (pin "2") (pinfunction "2_2") (pintype "passive"))
    )
    (net (code "34") (name "/USBDM") (class "Default")
      (node (ref "C4") (pin "1") (pinfunction "1_1") (pintype "passive"))
      (node (ref "IC1") (pin "16") (pinfunction "USBDM_16") (pintype "bidirectional"))
      (node (ref "IC7") (pin "P$3") (pinfunction "IO2_P$3") (pintype "bidirectional"))
    )
    (net (code "35") (name "/USBDP") (class "Default")
      (node (ref "C6") (pin "1") (pinfunction "1_1") (pintype "passive"))
      (node (ref "IC1") (pin "15") (pinfunction "USBDP_15") (pintype "bidirectional"))
      (node (ref "IC7") (pin "P$1") (pinfunction "IO1_P$1") (pintype "bidirectional"))
    )
    (net (code "36") (name "/USB_POWER") (class "Default")
      (node (ref "C3") (pin "1") (pinfunction "1_1") (pintype "passive"))
      (node (ref "IC7") (pin "P$5") (pinfunction "VBUS_P$5") (pintype "bidirectional"))
      (node (ref "L1") (pin "2") (pinfunction "2_2") (pintype "passive"))
      (node (ref "X6") (pin "P$1") (pinfunction "1_P$1") (pintype "bidirectional"))
    )
    (net (code "37") (name "/U_CLOCK_IN") (class "Default")
      (node (ref "IC12") (pin "2") (pinfunction "A_2") (pintype "bidirectional"))
      (node (ref "IC8") (pin "12") (pinfunction "PC2/OC0C/RXD0_12") (pintype "bidirectional"))
      (node (ref "R2") (pin "1") (pinfunction "1_1") (pintype "passive"))
      (node (ref "X8") (pin "4") (pinfunction "4_4") (pintype "passive"))
    )
    (net (code "38") (name "/U_HALL_EFFCT_IN") (class "Default")
      (node (ref "C42") (pin "2") (pinfunction "2_2") (pintype "passive"))
      (node (ref "IC8") (pin "41") (pinfunction "PA1/ADC1_41") (pintype "bidirectional"))
      (node (ref "R19") (pin "2") (pinfunction "2_2") (pintype "passive"))
    )
    (net (code "39") (name "/U_PH_A") (class "Default")
      (node (ref "IC2") (pin "4") (pinfunction "Y_4") (pintype "bidirectional"))
      (node (ref "IC8") (pin "14") (pinfunction "PC4/OC1A/~{SS}_14") (pintype "bidirectional"))
    )
    (net (code "40") (name "/U_PH_B") (class "Default")
      (node (ref "IC11") (pin "4") (pinfunction "Y_4") (pintype "bidirectional"))
      (node (ref "IC8") (pin "15") (pinfunction "PC5/OC1B/MOSI/XCK1_15") (pintype "bidirectional"))
    )
    (net (code "41") (name "/U_STEP_DIRECTION") (class "Default")
      (node (ref "IC5") (pin "2") (pinfunction "A_2") (pintype "bidirectional"))
      (node (ref "IC8") (pin "16") (pinfunction "PC6/MISO/RXD1_16") (pintype "bidirectional"))
      (node (ref "R13") (pin "2") (pinfunction "2_2") (pintype "passive"))
    )
    (net (code "42") (name "/U_STEP_ENABLE") (class "Default")
      (node (ref "IC6") (pin "2") (pinfunction "A_2") (pintype "bidirectional"))
      (node (ref "IC8") (pin "13") (pinfunction "PC3/OC0D/TXD0_13") (pintype "bidirectional"))
      (node (ref "R6") (pin "2") (pinfunction "2_2") (pintype "passive"))
    )
    (net (code "43") (name "/U_STEP_PULSE") (class "Default")
      (node (ref "IC4") (pin "2") (pinfunction "A_2") (pintype "bidirectional"))
      (node (ref "IC8") (pin "10") (pinfunction "PC0/OC0A/SDA_10") (pintype "bidirectional"))
      (node (ref "R12") (pin "2") (pinfunction "2_2") (pintype "passive"))
    )
    (net (code "44") (name "GND") (class "Default")
      (node (ref "C1") (pin "2") (pinfunction "2_2") (pintype "passive"))
      (node (ref "C10") (pin "2") (pinfunction "2_2") (pintype "passive"))
      (node (ref "C11") (pin "2") (pinfunction "2_2") (pintype "passive"))
      (node (ref "C12") (pin "2") (pinfunction "2_2") (pintype "passive"))
      (node (ref "C13") (pin "2") (pinfunction "2_2") (pintype "passive"))
      (node (ref "C14") (pin "2") (pinfunction "2_2") (pintype "passive"))
      (node (ref "C15") (pin "2") (pinfunction "2_2") (pintype "passive"))
      (node (ref "C16") (pin "2") (pinfunction "2_2") (pintype "passive"))
      (node (ref "C17") (pin "2") (pinfunction "2_2") (pintype "passive"))
      (node (ref "C18") (pin "2") (pinfunction "2_2") (pintype "passive"))
      (node (ref "C19") (pin "2") (pinfunction "2_2") (pintype "passive"))
      (node (ref "C2") (pin "2") (pinfunction "2_2") (pintype "passive"))
      (node (ref "C20") (pin "2") (pinfunction "2_2") (pintype "passive"))
      (node (ref "C21") (pin "2") (pinfunction "2_2") (pintype "passive"))
      (node (ref "C22") (pin "2") (pinfunction "2_2") (pintype "passive"))
      (node (ref "C23") (pin "2") (pinfunction "2_2") (pintype "passive"))
      (node (ref "C24") (pin "2") (pinfunction "2_2") (pintype "passive"))
      (node (ref "C25") (pin "2") (pinfunction "2_2") (pintype "passive"))
      (node (ref "C26") (pin "2") (pinfunction "2_2") (pintype "passive"))
      (node (ref "C27") (pin "2") (pinfunction "2_2") (pintype "passive"))
      (node (ref "C28") (pin "2") (pinfunction "2_2") (pintype "passive"))
      (node (ref "C29") (pin "2") (pinfunction "2_2") (pintype "passive"))
      (node (ref "C3") (pin "2") (pinfunction "2_2") (pintype "passive"))
      (node (ref "C30") (pin "2") (pinfunction "2_2") (pintype "passive"))
      (node (ref "C31") (pin "2") (pinfunction "2_2") (pintype "passive"))
      (node (ref "C4") (pin "2") (pinfunction "2_2") (pintype "passive"))
      (node (ref "C41") (pin "1") (pinfunction "1_1") (pintype "passive"))
      (node (ref "C42") (pin "1") (pinfunction "1_1") (pintype "passive"))
      (node (ref "C5") (pin "2") (pinfunction "2_2") (pintype "passive"))
      (node (ref "C6") (pin "2") (pinfunction "2_2") (pintype "passive"))
      (node (ref "C7") (pin "2") (pinfunction "2_2") (pintype "passive"))
      (node (ref "C8") (pin "2") (pinfunction "2_2") (pintype "passive"))
      (node (ref "C9") (pin "2") (pinfunction "2_2") (pintype "passive"))
      (node (ref "IC1") (pin "18") (pinfunction "GND_18") (pintype "power_in"))
      (node (ref "IC1") (pin "21") (pinfunction "GND_21") (pintype "power_in"))
      (node (ref "IC1") (pin "25") (pinfunction "GND_25") (pintype "power_in"))
      (node (ref "IC1") (pin "26") (pinfunction "TEST_26") (pintype "input"))
      (node (ref "IC1") (pin "7") (pinfunction "GND_7") (pintype "power_in"))
      (node (ref "IC10") (pin "2") (pinfunction "V-_2") (pintype "power_in"))
      (node (ref "IC11") (pin "3") (pinfunction "GND_3") (pintype "bidirectional"))
      (node (ref "IC12") (pin "3") (pinfunction "GND_3") (pintype "bidirectional"))
      (node (ref "IC13") (pin "3") (pinfunction "GND_3") (pintype "bidirectional"))
      (node (ref "IC14") (pin "3") (pinfunction "GND_3") (pintype "bidirectional"))
      (node (ref "IC15") (pin "3") (pinfunction "GND_3") (pintype "bidirectional"))
      (node (ref "IC16") (pin "3") (pinfunction "GND_3") (pintype "bidirectional"))
      (node (ref "IC17") (pin "3") (pinfunction "GND_3") (pintype "bidirectional"))
      (node (ref "IC18") (pin "3") (pinfunction "GND_3") (pintype "bidirectional"))
      (node (ref "IC2") (pin "3") (pinfunction "GND_3") (pintype "bidirectional"))
      (node (ref "IC3") (pin "2") (pinfunction "GND_2") (pintype "bidirectional"))
      (node (ref "IC4") (pin "3") (pinfunction "GND_3") (pintype "bidirectional"))
      (node (ref "IC5") (pin "3") (pinfunction "GND_3") (pintype "bidirectional"))
      (node (ref "IC6") (pin "3") (pinfunction "GND_3") (pintype "bidirectional"))
      (node (ref "IC7") (pin "P$2") (pinfunction "GND_P$2") (pintype "bidirectional"))
      (node (ref "IC8") (pin "18") (pinfunction "GND_18") (pintype "power_in"))
      (node (ref "IC8") (pin "30") (pinfunction "GND_30") (pintype "power_in"))
      (node (ref "IC8") (pin "38") (pinfunction "GND_38") (pintype "power_in"))
      (node (ref "IC8") (pin "42") (pinfunction "PA2/ADC2_42") (pintype "bidirectional"))
      (node (ref "IC8") (pin "8") (pinfunction "GND_8") (pintype "power_in"))
      (node (ref "IC9") (pin "2") (pinfunction "GND_2") (pintype "bidirectional"))
      (node (ref "OSC1") (pin "P$2") (pinfunction "GND_P$2") (pintype "passive"))
      (node (ref "R1") (pin "1") (pinfunction "1_1") (pintype "passive"))
      (node (ref "R10") (pin "1") (pinfunction "1_1") (pintype "passive"))
      (node (ref "R11") (pin "1") (pinfunction "1_1") (pintype "passive"))
      (node (ref "R12") (pin "1") (pinfunction "1_1") (pintype "passive"))
      (node (ref "R13") (pin "1") (pinfunction "1_1") (pintype "passive"))
      (node (ref "R14") (pin "1") (pinfunction "1_1") (pintype "passive"))
      (node (ref "R21") (pin "1") (pinfunction "1_1") (pintype "passive"))
      (node (ref "R3") (pin "1") (pinfunction "1_1") (pintype "passive"))
      (node (ref "R6") (pin "1") (pinfunction "1_1") (pintype "passive"))
      (node (ref "R7") (pin "1") (pinfunction "1_1") (pintype "passive"))
      (node (ref "SV2") (pin "6") (pinfunction "6_6") (pintype "passive"))
      (node (ref "TP10") (pin "TP") (pinfunction "TP_TP") (pintype "input"))
      (node (ref "TP11") (pin "TP") (pinfunction "TP_TP") (pintype "input"))
      (node (ref "X1") (pin "5") (pinfunction "5_5") (pintype "passive"))
      (node (ref "X10") (pin "1") (pinfunction "S_1") (pintype "passive"))
      (node (ref "X2") (pin "1") (pinfunction "S_1") (pintype "passive"))
      (node (ref "X3") (pin "1") (pinfunction "S_1") (pintype "passive"))
      (node (ref "X4") (pin "1") (pinfunction "S_1") (pintype "passive"))
      (node (ref "X5") (pin "1") (pinfunction "S_1") (pintype "passive"))
      (node (ref "X6") (pin "P$5") (pinfunction "5_P$5") (pintype "bidirectional"))
      (node (ref "X7") (pin "P2") (pinfunction "2_P2") (pintype "passive"))
      (node (ref "X7") (pin "P3") (pinfunction "3_P3") (pintype "passive"))
      (node (ref "X8") (pin "5") (pinfunction "5_5") (pintype "passive"))
      (node (ref "X9") (pin "1") (pinfunction "S_1") (pintype "passive"))
    )
    (net (code "45") (name "Net-(C15-Pad1)") (class "Default")
      (node (ref "C15") (pin "1") (pinfunction "1_1") (pintype "passive"))
      (node (ref "R4") (pin "2") (pinfunction "2_2") (pintype "passive"))
      (node (ref "R9") (pin "1") (pinfunction "1_1") (pintype "passive"))
    )
    (net (code "46") (name "Net-(C41-Pad2)") (class "Default")
      (node (ref "C41") (pin "2") (pinfunction "2_2") (pintype "passive"))
      (node (ref "R17") (pin "2") (pinfunction "2_2") (pintype "passive"))
      (node (ref "R19") (pin "1") (pinfunction "1_1") (pintype "passive"))
    )
    (net (code "47") (name "Net-(IC1-3V3OUT)") (class "Default")
      (node (ref "C7") (pin "1") (pinfunction "1_1") (pintype "passive"))
      (node (ref "IC1") (pin "17") (pinfunction "3V3OUT_17") (pintype "output"))
    )
    (net (code "48") (name "Net-(IC1-~{RESET})") (class "Default")
      (node (ref "IC1") (pin "19") (pinfunction "~{RESET}_19") (pintype "input"))
      (node (ref "R18") (pin "2") (pinfunction "2_2") (pintype "passive"))
    )
    (net (code "49") (name "Net-(IC8-AVCC)") (class "Default")
      (node (ref "C16") (pin "1") (pinfunction "1_1") (pintype "passive"))
      (node (ref "IC8") (pin "39") (pinfunction "AVCC_39") (pintype "power_in"))
      (node (ref "L3") (pin "1") (pinfunction "1_1") (pintype "passive"))
    )
    (net (code "50") (name "Net-(IC8-OC0B{slash}XCK0{slash}PD1)") (class "Default")
      (node (ref "IC8") (pin "21") (pinfunction "OC0B/XCK0/PD1_21") (pintype "bidirectional"))
      (node (ref "TP9") (pin "TP") (pinfunction "TP_TP") (pintype "input"))
    )
    (net (code "51") (name "Net-(IC8-PA4{slash}ADC4)") (class "Default")
      (node (ref "IC8") (pin "44") (pinfunction "PA4/ADC4_44") (pintype "bidirectional"))
      (node (ref "TP4") (pin "TP") (pinfunction "TP_TP") (pintype "input"))
    )
    (net (code "52") (name "Net-(IC8-PA5{slash}ADC5)") (class "Default")
      (node (ref "IC8") (pin "1") (pinfunction "PA5/ADC5_1") (pintype "bidirectional"))
      (node (ref "TP5") (pin "TP") (pinfunction "TP_TP") (pintype "input"))
    )
    (net (code "53") (name "Net-(IC8-PB2{slash}ADC10{slash}DAC0)") (class "Default")
      (node (ref "IC8") (pin "6") (pinfunction "PB2/ADC10/DAC0_6") (pintype "bidirectional"))
      (node (ref "TP6") (pin "TP") (pinfunction "TP_TP") (pintype "input"))
    )
    (net (code "54") (name "Net-(IC8-PC1{slash}OC0B{slash}XCK0{slash}SCL)") (class "Default")
      (node (ref "IC8") (pin "11") (pinfunction "PC1/OC0B/XCK0/SCL_11") (pintype "bidirectional"))
      (node (ref "TP8") (pin "TP") (pinfunction "TP_TP") (pintype "input"))
    )
    (net (code "55") (name "Net-(IC8-PR1{slash}XTAL1)") (class "Default")
      (node (ref "IC8") (pin "37") (pinfunction "PR1/XTAL1_37") (pintype "bidirectional"))
      (node (ref "OSC1") (pin "P$3") (pinfunction "OUTPUT_P$3") (pintype "passive"))
    )
    (net (code "56") (name "Net-(IC9-OUT)") (class "Default")
      (node (ref "C24") (pin "1") (pinfunction "1_1") (pintype "passive"))
      (node (ref "IC9") (pin "5") (pinfunction "OUT_5") (pintype "bidirectional"))
      (node (ref "R5") (pin "1") (pinfunction "1_1") (pintype "passive"))
    )
    (net (code "57") (name "Net-(IC10-+IN)") (class "Default")
      (node (ref "IC10") (pin "3") (pinfunction "+IN_3") (pintype "input"))
      (node (ref "R20") (pin "1") (pinfunction "1_1") (pintype "passive"))
      (node (ref "R21") (pin "2") (pinfunction "2_2") (pintype "passive"))
    )
    (net (code "58") (name "Net-(IC10--IN)") (class "Default")
      (node (ref "IC10") (pin "1") (pinfunction "OUT_1") (pintype "output"))
      (node (ref "IC10") (pin "4") (pinfunction "-IN_4") (pintype "input"))
      (node (ref "R17") (pin "1") (pinfunction "1_1") (pintype "passive"))
    )
    (net (code "59") (name "Net-(R1-Pad2)") (class "Default")
      (node (ref "R1") (pin "2") (pinfunction "2_2") (pintype "passive"))
      (node (ref "STATE") (pin "C") (pinfunction "C_C") (pintype "passive"))
    )
    (net (code "60") (name "Net-(R2-Pad2)") (class "Default")
      (node (ref "R2") (pin "2") (pinfunction "2_2") (pintype "passive"))
      (node (ref "R5") (pin "2") (pinfunction "2_2") (pintype "passive"))
      (node (ref "X8") (pin "1") (pinfunction "1_1") (pintype "passive"))
    )
    (net (code "61") (name "Net-(X6-2)") (class "Default")
      (node (ref "IC7") (pin "P$4") (pinfunction "IO2_P$4") (pintype "bidirectional"))
      (node (ref "X6") (pin "P$2") (pinfunction "2_P$2") (pintype "bidirectional"))
    )
    (net (code "62") (name "Net-(X6-3)") (class "Default")
      (node (ref "IC7") (pin "P$6") (pinfunction "IO1_P$6") (pintype "bidirectional"))
      (node (ref "X6") (pin "P$3") (pinfunction "3_P$3") (pintype "bidirectional"))
    )
    (net (code "63") (name "Net-(X6-P$3)") (class "Default")
      (node (ref "C2") (pin "1") (pinfunction "1_1") (pintype "passive"))
      (node (ref "X6") (pin "SHIELD_3") (pinfunction "P$3_SHIELD_3") (pintype "bidirectional"))
    )
    (net (code "64") (name "Net-(X6-P$4)") (class "Default")
      (node (ref "R3") (pin "2") (pinfunction "2_2") (pintype "passive"))
      (node (ref "X6") (pin "SHIELD_4") (pinfunction "P$4_SHIELD_4") (pintype "bidirectional"))
    )
    (net (code "65") (name "VDD") (class "Default")
      (node (ref "X1") (pin "1") (pinfunction "1_1") (pintype "passive"))
      (node (ref "X7") (pin "P1") (pinfunction "1_P1") (pintype "passive"))
    )
    (net (code "66") (name "unconnected-(IC1-CBUS0-Pad23)") (class "Default")
      (node (ref "IC1") (pin "23") (pinfunction "CBUS0_23") (pintype "bidirectional"))
    )
    (net (code "67") (name "unconnected-(IC1-CBUS1-Pad22)") (class "Default")
      (node (ref "IC1") (pin "22") (pinfunction "CBUS1_22") (pintype "bidirectional"))
    )
    (net (code "68") (name "unconnected-(IC1-CBUS2-Pad13)") (class "Default")
      (node (ref "IC1") (pin "13") (pinfunction "CBUS2_13") (pintype "bidirectional"))
    )
    (net (code "69") (name "unconnected-(IC1-CBUS3-Pad14)") (class "Default")
      (node (ref "IC1") (pin "14") (pinfunction "CBUS3_14") (pintype "bidirectional"))
    )
    (net (code "70") (name "unconnected-(IC1-CBUS4-Pad12)") (class "Default")
      (node (ref "IC1") (pin "12") (pinfunction "CBUS4_12") (pintype "bidirectional"))
    )
    (net (code "71") (name "unconnected-(IC1-OSCI-Pad27)") (class "Default")
      (node (ref "IC1") (pin "27") (pinfunction "OSCI_27") (pintype "input"))
    )
    (net (code "72") (name "unconnected-(IC1-OSCO-Pad28)") (class "Default")
      (node (ref "IC1") (pin "28") (pinfunction "OSCO_28") (pintype "output"))
    )
    (net (code "73") (name "unconnected-(IC1-~{DCD}-Pad10)") (class "Default")
      (node (ref "IC1") (pin "10") (pinfunction "~{DCD}_10") (pintype "input"))
    )
    (net (code "74") (name "unconnected-(IC1-~{DSR}-Pad9)") (class "Default")
      (node (ref "IC1") (pin "9") (pinfunction "~{DSR}_9") (pintype "input"))
    )
    (net (code "75") (name "unconnected-(IC1-~{DTR}-Pad2)") (class "Default")
      (node (ref "IC1") (pin "2") (pinfunction "~{DTR}_2") (pintype "output"))
    )
    (net (code "76") (name "unconnected-(IC1-~{RI}-Pad6)") (class "Default")
      (node (ref "IC1") (pin "6") (pinfunction "~{RI}_6") (pintype "input"))
    )
    (net (code "77") (name "unconnected-(IC3-N{slash}C-Pad4)") (class "Default")
      (node (ref "IC3") (pin "4") (pinfunction "N/C_4") (pintype "bidirectional"))
    )
    (net (code "78") (name "unconnected-(IC8-D+{slash}TXD1{slash}SCK{slash}PD7-Pad27)") (class "Default")
      (node (ref "IC8") (pin "27") (pinfunction "D+/TXD1/SCK/PD7_27") (pintype "bidirectional"))
    )
    (net (code "79") (name "unconnected-(IC8-OC0A{slash}PD0-Pad20)") (class "Default")
      (node (ref "IC8") (pin "20") (pinfunction "OC0A/PD0_20") (pintype "bidirectional"))
    )
    (net (code "80") (name "unconnected-(IC8-OC1A{slash}~{SS}{slash}PD4-Pad24)") (class "Default")
      (node (ref "IC8") (pin "24") (pinfunction "OC1A/~{SS}/PD4_24") (pintype "bidirectional"))
    )
    (net (code "81") (name "unconnected-(IC8-PA3{slash}ADC3-Pad43)") (class "Default")
      (node (ref "IC8") (pin "43") (pinfunction "PA3/ADC3_43") (pintype "bidirectional"))
    )
    (net (code "82") (name "unconnected-(IC8-PA6{slash}ADC6{slash}AC1-OUT-Pad2)") (class "Default")
      (node (ref "IC8") (pin "2") (pinfunction "PA6/ADC6/AC1-OUT_2") (pintype "bidirectional"))
    )
    (net (code "83") (name "unconnected-(IC9-N{slash}C-Pad4)") (class "Default")
      (node (ref "IC9") (pin "4") (pinfunction "N/C_4") (pintype "bidirectional"))
    )
    (net (code "84") (name "unconnected-(OSC1-STANDBY#-PadP$1)") (class "Default")
      (node (ref "OSC1") (pin "P$1") (pinfunction "STANDBY#_P$1") (pintype "passive"))
    )
    (net (code "85") (name "unconnected-(SV2-Pad3)") (class "Default")
      (node (ref "SV2") (pin "3") (pinfunction "3_3") (pintype "passive"))
    )
    (net (code "86") (name "unconnected-(SV2-Pad4)") (class "Default")
      (node (ref "SV2") (pin "4") (pinfunction "4_4") (pintype "passive"))
    )
    (net (code "87") (name "unconnected-(X2D-S-Pad4)") (class "Default")
      (node (ref "X2") (pin "4") (pinfunction "S_4") (pintype "passive"))
    )
    (net (code "88") (name "unconnected-(X6-4-PadP$4)") (class "Default")
      (node (ref "X6") (pin "P$4") (pinfunction "4_P$4") (pintype "bidirectional"))
    )
    (net (code "89") (name "unconnected-(X6-P$1-PadSHIELD_1)") (class "Default")
      (node (ref "X6") (pin "SHIELD_1") (pinfunction "P$1_SHIELD_1") (pintype "bidirectional"))
    )
    (net (code "90") (name "unconnected-(X6-P$2-PadSHIELD_2)") (class "Default")
      (node (ref "X6") (pin "SHIELD_2") (pinfunction "P$2_SHIELD_2") (pintype "bidirectional"))
    )
  )
)
